# LM2736.net
KiCad netlist of a schematic drawn in Altium Designer
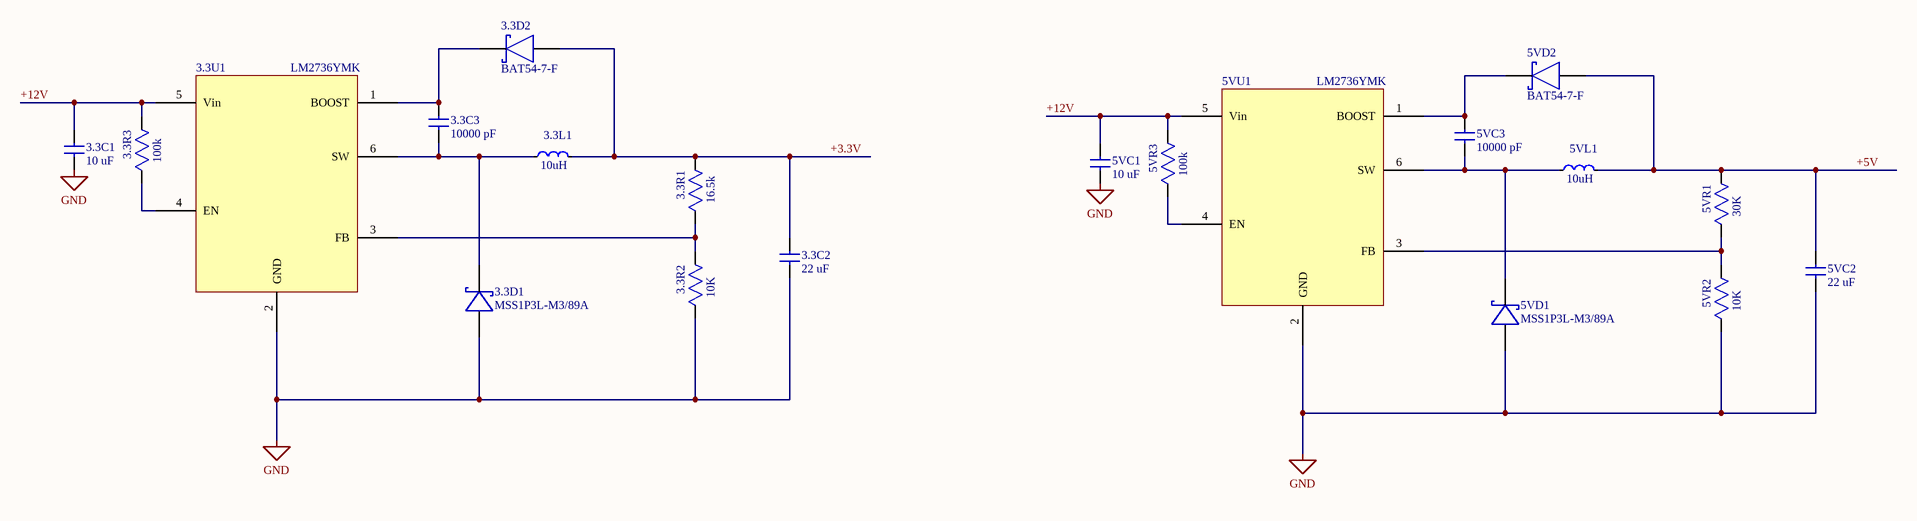
[diagram p0: LM2736.SchDoc]

(export (version "E")
  (design (tool "Eeschema 10.0.6"))
  (components
    (comp (ref "3.3C1")
      (value "10 uF")
      (footprint "0805_Capacitor")
      (description "CAP CERM 10 uF")
      (fields (field (name "Comment") "CAP 10 uF"))
      (libsource (lib "c3_SchLib") (part "C_0805_10uF"))
    )
    (comp (ref "3.3C2")
      (value "22 uF")
      (footprint "0805_Capacitor")
      (description "CAP CER 22UF 16V X5R 10% 0805")
      (fields
        (field (name "MANUFACTURER") "TDK")
        (field (name "Comment") "CAP 22 uF")
        (field (name "SVP CREATOR") "Matt Rogge")
      )
      (libsource (lib "c3_SchLib") (part "C_0805_22uF"))
    )
    (comp (ref "3.3C3")
      (value "10000 pF")
      (footprint "0805_Capacitor")
      (description "CAP CERM 10000PF")
      (fields
        (field (name "MANUFACTURER") "AVX")
        (field (name "Comment") "CAP 10000pF")
        (field (name "SVP CREATOR") "Jonathan Nutzmann")
      )
      (libsource (lib "c3_SchLib") (part "C_0805_10000pF"))
    )
    (comp (ref "3.3D1")
      (value "SCHOTTKY 30V 1A")
      (footprint "MicroSMP")
      (description "DIODE SCHOTTKY 1A 30V MICROSMP")
      (fields
        (field (name "MANUFACTURER") "Vishay")
        (field (name "VOLTAGE") "30V")
        (field (name "MANUFACTURER PN") "MSS1P3L-M3/89A")
        (field (name "SVP CREATOR") "Brett Paulsen")
      )
      (libsource (lib "c3_SchLib") (part "D_Schottky_MSS1P3L-M3/89A"))
    )
    (comp (ref "3.3D2")
      (value "SCHOTTKY 30V 1A")
      (footprint "SOT-23")
      (description "DIODE SCHOTTKY 30V 200MW SOT23-3")
      (fields
        (field (name "MANUFACTURER") "Diodes Inc")
        (field (name "VOLTAGE") "30V")
        (field (name "MANUFACTURER PN") "BAT54-7-F")
        (field (name "SVP CREATOR") "Brett Paulsen")
      )
      (libsource (lib "c3_SchLib") (part "D_Schottky_BAT54-7-F"))
    )
    (comp (ref "3.3L1")
      (value "10uH")
      (footprint "LPS4018_inductor")
      (description "INDUCTOR PWR 10UH 20% SHIELD SMD")
      (fields
        (field (name "MANUFACTURER") "Coilcraft")
        (field (name "Comment") "L_10uH_20%")
        (field (name "SVP CREATOR") "Brett Paulsen")
      )
      (libsource (lib "c3_SchLib") (part "L_10uH_20%"))
    )
    (comp (ref "3.3R1")
      (value "16.5k")
      (footprint "0805_Resistor")
      (description "RES 16.5k OHM 1/8W 1% 0805 SMD")
      (fields (field (name "Comment") "R_0805_16.5k_1%") (field (name "SVP CREATOR") "Brett Paulsen"))
      (libsource (lib "c3_SchLib") (part "R_0805_16.5k_1%"))
    )
    (comp (ref "3.3R2")
      (value "10K")
      (footprint "0805_Resistor")
      (description "RES 10K OHM 1/8W 1% 0805 SMD")
      (fields (field (name "Comment") "R_0805_10k_1%") (field (name "SVP CREATOR") "Jonathan Nutzmann"))
      (libsource (lib "c3_SchLib") (part "R_0805_10K_1%"))
    )
    (comp (ref "3.3R3")
      (value "100k")
      (footprint "0805_Resistor")
      (description "RES 100K OHM 1/8W 1% 0805 SMD")
      (fields
        (field (name "MANUFACTURER") "Rohm Semiconductor")
        (field (name "Comment") "R_0805_100k_1%")
        (field (name "SVP CREATOR") "Jonathan Nutzmann")
      )
      (libsource (lib "c3_SchLib") (part "R_0805_100k_1%"))
    )
    (comp (ref "3.3U1")
      (value "Short Part Description")
      (footprint "TSOT95P285X100-6M")
      (description "IC REG PWM STPDWN 750 mA")
      (fields
        (field (name "MANUFACTURER") "National Semiconductor (TI?)")
        (field (name "MANUFACTURER PN") "LM2736YMK")
        (field (name "SVP CREATOR") "Brett Paulsen")
        (field (name "SVP REVIEWER 1") "Arlo Siemsen")
      )
      (libsource (lib "c3_SchLib") (part "U_LM2736YMK"))
    )
    (comp (ref "5VC1")
      (value "10 uF")
      (footprint "0805_Capacitor")
      (description "CAP CERM 10 uF")
      (fields (field (name "Comment") "CAP 10 uF"))
      (libsource (lib "c3_SchLib") (part "C_0805_10uF"))
    )
    (comp (ref "5VC2")
      (value "22 uF")
      (footprint "0805_Capacitor")
      (description "CAP CER 22UF 16V X5R 10% 0805")
      (fields
        (field (name "MANUFACTURER") "TDK")
        (field (name "Comment") "CAP 22 uF")
        (field (name "SVP CREATOR") "Matt Rogge")
      )
      (libsource (lib "c3_SchLib") (part "C_0805_22uF"))
    )
    (comp (ref "5VC3")
      (value "10000 pF")
      (footprint "0805_Capacitor")
      (description "CAP CERM 10000PF")
      (fields
        (field (name "MANUFACTURER") "AVX")
        (field (name "Comment") "CAP 10000pF")
        (field (name "SVP CREATOR") "Jonathan Nutzmann")
      )
      (libsource (lib "c3_SchLib") (part "C_0805_10000pF"))
    )
    (comp (ref "5VD1")
      (value "SCHOTTKY 30V 1A")
      (footprint "MicroSMP")
      (description "DIODE SCHOTTKY 1A 30V MICROSMP")
      (fields
        (field (name "MANUFACTURER") "Vishay")
        (field (name "VOLTAGE") "30V")
        (field (name "MANUFACTURER PN") "MSS1P3L-M3/89A")
        (field (name "SVP CREATOR") "Brett Paulsen")
      )
      (libsource (lib "c3_SchLib") (part "D_Schottky_MSS1P3L-M3/89A"))
    )
    (comp (ref "5VD2")
      (value "SCHOTTKY 30V 1A")
      (footprint "SOT-23")
      (description "DIODE SCHOTTKY 30V 200MW SOT23-3")
      (fields
        (field (name "MANUFACTURER") "Diodes Inc")
        (field (name "VOLTAGE") "30V")
        (field (name "MANUFACTURER PN") "BAT54-7-F")
        (field (name "SVP CREATOR") "Brett Paulsen")
      )
      (libsource (lib "c3_SchLib") (part "D_Schottky_BAT54-7-F"))
    )
    (comp (ref "5VL1")
      (value "10uH")
      (footprint "LPS4018_inductor")
      (description "INDUCTOR PWR 10UH 20% SHIELD SMD")
      (fields
        (field (name "MANUFACTURER") "Coilcraft")
        (field (name "Comment") "L_10uH_20%")
        (field (name "SVP CREATOR") "Brett Paulsen")
      )
      (libsource (lib "c3_SchLib") (part "L_10uH_20%"))
    )
    (comp (ref "5VR1")
      (value "30K")
      (footprint "0805_Resistor")
      (description "RES 30K OHM 1/8W 1% 0805 SMD")
      (fields (field (name "Comment") "R_0805_30K_1%") (field (name "SVP CREATOR") "Brett Paulsen"))
      (libsource (lib "c3_SchLib") (part "R_0805_30K_1%"))
    )
    (comp (ref "5VR2")
      (value "10K")
      (footprint "0805_Resistor")
      (description "RES 10K OHM 1/8W 1% 0805 SMD")
      (fields (field (name "Comment") "R_0805_10k_1%") (field (name "SVP CREATOR") "Jonathan Nutzmann"))
      (libsource (lib "c3_SchLib") (part "R_0805_10K_1%"))
    )
    (comp (ref "5VR3")
      (value "100k")
      (footprint "0805_Resistor")
      (description "RES 100K OHM 1/8W 1% 0805 SMD")
      (fields
        (field (name "MANUFACTURER") "Rohm Semiconductor")
        (field (name "Comment") "R_0805_100k_1%")
        (field (name "SVP CREATOR") "Jonathan Nutzmann")
      )
      (libsource (lib "c3_SchLib") (part "R_0805_100k_1%"))
    )
    (comp (ref "5VU1")
      (value "Short Part Description")
      (footprint "TSOT95P285X100-6M")
      (description "IC REG PWM STPDWN 750 mA")
      (fields
        (field (name "MANUFACTURER") "National Semiconductor (TI?)")
        (field (name "MANUFACTURER PN") "LM2736YMK")
        (field (name "SVP CREATOR") "Brett Paulsen")
        (field (name "SVP REVIEWER 1") "Arlo Siemsen")
      )
      (libsource (lib "c3_SchLib") (part "U_LM2736YMK"))
    )
  )
  (nets
    (net (code "1") (name "/+3.3V") (class "Default")
      (node (ref "3.3C2") (pin "1") (pinfunction "1_1") (pintype "passive"))
      (node (ref "3.3D2") (pin "1") (pinfunction "1_1") (pintype "passive"))
      (node (ref "3.3L1") (pin "2") (pinfunction "2_2") (pintype "passive"))
      (node (ref "3.3R1") (pin "1") (pinfunction "1_1") (pintype "passive"))
    )
    (net (code "2") (name "/+5V") (class "Default")
      (node (ref "5VC2") (pin "1") (pinfunction "1_1") (pintype "passive"))
      (node (ref "5VD2") (pin "1") (pinfunction "1_1") (pintype "passive"))
      (node (ref "5VL1") (pin "2") (pinfunction "2_2") (pintype "passive"))
      (node (ref "5VR1") (pin "1") (pinfunction "1_1") (pintype "passive"))
    )
    (net (code "3") (name "/+12V") (class "Default")
      (node (ref "3.3C1") (pin "1") (pinfunction "1_1") (pintype "passive"))
      (node (ref "3.3R3") (pin "1") (pinfunction "1_1") (pintype "passive"))
      (node (ref "3.3U1") (pin "5") (pinfunction "Vin_5") (pintype "passive"))
      (node (ref "5VC1") (pin "1") (pinfunction "1_1") (pintype "passive"))
      (node (ref "5VR3") (pin "1") (pinfunction "1_1") (pintype "passive"))
      (node (ref "5VU1") (pin "5") (pinfunction "Vin_5") (pintype "passive"))
    )
    (net (code "4") (name "GND") (class "Default")
      (node (ref "3.3C1") (pin "2") (pinfunction "2_2") (pintype "passive"))
      (node (ref "3.3C2") (pin "2") (pinfunction "2_2") (pintype "passive"))
      (node (ref "3.3D1") (pin "1") (pinfunction "1_1") (pintype "passive"))
      (node (ref "3.3R2") (pin "2") (pinfunction "2_2") (pintype "passive"))
      (node (ref "3.3U1") (pin "2") (pinfunction "GND_2") (pintype "passive"))
      (node (ref "5VC1") (pin "2") (pinfunction "2_2") (pintype "passive"))
      (node (ref "5VC2") (pin "2") (pinfunction "2_2") (pintype "passive"))
      (node (ref "5VD1") (pin "1") (pinfunction "1_1") (pintype "passive"))
      (node (ref "5VR2") (pin "2") (pinfunction "2_2") (pintype "passive"))
      (node (ref "5VU1") (pin "2") (pinfunction "GND_2") (pintype "passive"))
    )
    (net (code "5") (name "Net-(3.3U1-BOOST)") (class "Default")
      (node (ref "3.3C3") (pin "1") (pinfunction "1_1") (pintype "passive"))
      (node (ref "3.3D2") (pin "3") (pinfunction "3_3") (pintype "passive"))
      (node (ref "3.3U1") (pin "1") (pinfunction "BOOST_1") (pintype "passive"))
    )
    (net (code "6") (name "Net-(3.3U1-EN)") (class "Default")
      (node (ref "3.3R3") (pin "2") (pinfunction "2_2") (pintype "passive"))
      (node (ref "3.3U1") (pin "4") (pinfunction "EN_4") (pintype "passive"))
    )
    (net (code "7") (name "Net-(3.3U1-FB)") (class "Default")
      (node (ref "3.3R1") (pin "2") (pinfunction "2_2") (pintype "passive"))
      (node (ref "3.3R2") (pin "1") (pinfunction "1_1") (pintype "passive"))
      (node (ref "3.3U1") (pin "3") (pinfunction "FB_3") (pintype "passive"))
    )
    (net (code "8") (name "Net-(3.3U1-SW)") (class "Default")
      (node (ref "3.3C3") (pin "2") (pinfunction "2_2") (pintype "passive"))
      (node (ref "3.3D1") (pin "2") (pinfunction "2_2") (pintype "passive"))
      (node (ref "3.3L1") (pin "1") (pinfunction "1_1") (pintype "passive"))
      (node (ref "3.3U1") (pin "6") (pinfunction "SW_6") (pintype "passive"))
    )
    (net (code "9") (name "Net-(5VU1-BOOST)") (class "Default")
      (node (ref "5VC3") (pin "1") (pinfunction "1_1") (pintype "passive"))
      (node (ref "5VD2") (pin "3") (pinfunction "3_3") (pintype "passive"))
      (node (ref "5VU1") (pin "1") (pinfunction "BOOST_1") (pintype "passive"))
    )
    (net (code "10") (name "Net-(5VU1-EN)") (class "Default")
      (node (ref "5VR3") (pin "2") (pinfunction "2_2") (pintype "passive"))
      (node (ref "5VU1") (pin "4") (pinfunction "EN_4") (pintype "passive"))
    )
    (net (code "11") (name "Net-(5VU1-FB)") (class "Default")
      (node (ref "5VR1") (pin "2") (pinfunction "2_2") (pintype "passive"))
      (node (ref "5VR2") (pin "1") (pinfunction "1_1") (pintype "passive"))
      (node (ref "5VU1") (pin "3") (pinfunction "FB_3") (pintype "passive"))
    )
    (net (code "12") (name "Net-(5VU1-SW)") (class "Default")
      (node (ref "5VC3") (pin "2") (pinfunction "2_2") (pintype "passive"))
      (node (ref "5VD1") (pin "2") (pinfunction "2_2") (pintype "passive"))
      (node (ref "5VL1") (pin "1") (pinfunction "1_1") (pintype "passive"))
      (node (ref "5VU1") (pin "6") (pinfunction "SW_6") (pintype "passive"))
    )
  )
)
